# Sheet1.net
KiCad netlist of a schematic drawn in Altium Designer
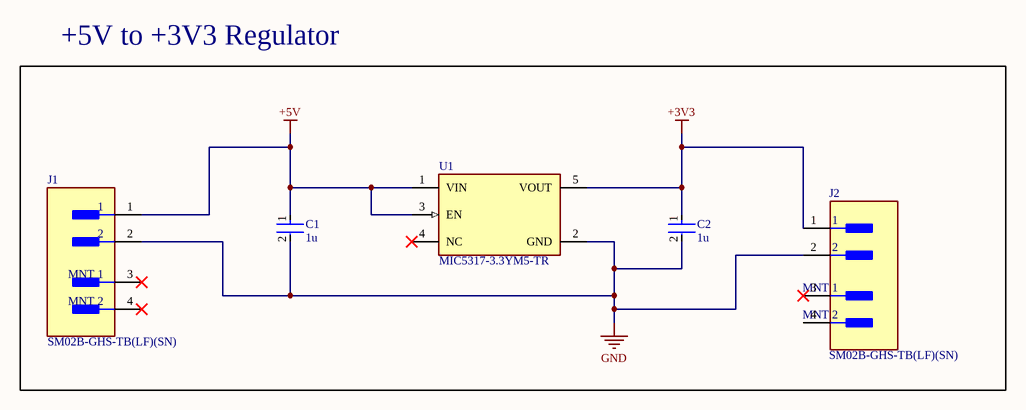
[diagram p0: Sheet1.SchDoc]

(export (version "E")
  (design (tool "Eeschema 10.0.6"))
  (components
    (comp (ref "C1")
      (value "1u")
      (footprint "FP-CC0805-0_85-MFG")
      (description "CAP CER 1UF 10V X7R 0805")
      (fields
        (field (name "MANUFACTURER") "Yageo")
        (field (name "OCTOPART") "https://octopart.com/cc0805kkx7r6bb105-yageo-42522859")
      )
      (libsource (lib "Altium Content Vault") (part "11868f565c42a9108669ba33697ecf6"))
    )
    (comp (ref "C2")
      (value "1u")
      (footprint "FP-CC0805-0_85-MFG")
      (description "CAP CER 1UF 10V X7R 0805")
      (fields
        (field (name "MANUFACTURER") "Yageo")
        (field (name "OCTOPART") "https://octopart.com/cc0805kkx7r6bb105-yageo-42522859")
      )
      (libsource (lib "Altium Content Vault") (part "11868f565c42a9108669ba33697ecf6"))
    )
    (comp (ref "J1")
      (value "SM02B-GHS-TB(LF)(SN)")
      (footprint "FP-SM02B-GHS-TB_LF_SN-MFG")
      (description "CONN HEADER SMD R/A 2POS 1.25MM")
      (libsource (lib "Altium Content Vault") (part "56ec3178a87b3978bdc1b3682cd516a"))
    )
    (comp (ref "J2")
      (value "SM02B-GHS-TB(LF)(SN)")
      (footprint "FP-SM02B-GHS-TB_LF_SN-MFG")
      (description "CONN HEADER SMD R/A 2POS 1.25MM")
      (libsource (lib "") (part "56ec3178a87b3978bdc1b3682cd516a_1"))
    )
    (comp (ref "U1")
      (value "MIC5317-3.3YM5-TR")
      (footprint "FP-SOT23-5LD-PL-1-MFG")
      (description "IC REG LINEAR 3.3V 150MA SOT23-5")
      (libsource (lib "Altium Content Vault") (part "0a093dae7315cdc977fd108dde87457"))
    )
  )
  (nets
    (net (code "1") (name "+3V3") (class "Default")
      (node (ref "C2") (pin "1") (pinfunction "1_1") (pintype "passive"))
      (node (ref "J2") (pin "1") (pinfunction "1_1") (pintype "passive"))
      (node (ref "U1") (pin "5") (pinfunction "VOUT_5") (pintype "power_in"))
    )
    (net (code "2") (name "+5V") (class "Default")
      (node (ref "C1") (pin "1") (pinfunction "1_1") (pintype "passive"))
      (node (ref "J1") (pin "1") (pinfunction "1_1") (pintype "passive"))
      (node (ref "U1") (pin "1") (pinfunction "VIN_1") (pintype "power_in"))
      (node (ref "U1") (pin "3") (pinfunction "EN_3") (pintype "input"))
    )
    (net (code "3") (name "GND") (class "Default")
      (node (ref "C1") (pin "2") (pinfunction "2_2") (pintype "passive"))
      (node (ref "C2") (pin "2") (pinfunction "2_2") (pintype "passive"))
      (node (ref "J1") (pin "2") (pinfunction "2_2") (pintype "passive"))
      (node (ref "J2") (pin "2") (pinfunction "2_2") (pintype "passive"))
      (node (ref "U1") (pin "2") (pinfunction "GND_2") (pintype "power_in"))
    )
    (net (code "4") (name "unconnected-(J1-MNT_1-Pad3)") (class "Default")
      (node (ref "J1") (pin "3") (pinfunction "MNT_1_3") (pintype "passive+no_connect"))
    )
    (net (code "5") (name "unconnected-(J1-MNT_2-Pad4)") (class "Default")
      (node (ref "J1") (pin "4") (pinfunction "MNT_2_4") (pintype "passive+no_connect"))
    )
    (net (code "6") (name "unconnected-(J2-MNT_1-Pad3)") (class "Default")
      (node (ref "J2") (pin "3") (pinfunction "MNT_1_3") (pintype "passive+no_connect"))
    )
    (net (code "7") (name "unconnected-(J2-MNT_2-Pad4)") (class "Default")
      (node (ref "J2") (pin "4") (pinfunction "MNT_2_4") (pintype "passive"))
    )
    (net (code "8") (name "unconnected-(U1-NC-Pad4)") (class "Default")
      (node (ref "U1") (pin "4") (pinfunction "NC_4") (pintype "passive+no_connect"))
    )
  )
)
